# nightlight_bjt_b1.net
KiCad netlist of a schematic drawn in EAGLE
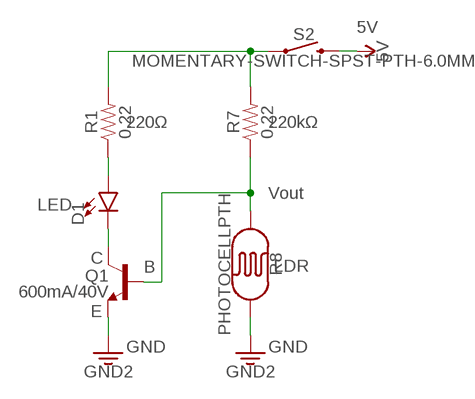
[diagram p0: schematic, sheet 1]

(export (version "E")
  (design (tool "Eeschema 10.0.6"))
  (components
    (comp (ref "D1")
      (value "LED5MM")
      (footprint "eagle-import:LED_5MM")
      (libsource (lib "eagle-import") (part "LED5MM"))
    )
    (comp (ref "Q1")
      (value "600mA/40V")
      (footprint "eagle-import:TO-92")
      (libsource (lib "eagle-import") (part "TRANS_NPN-P2N2222A"))
    )
    (comp (ref "R1")
      (value "0.22")
      (footprint "eagle-import:0805")
      (libsource (lib "eagle-import") (part "0.22OHM-0805-1/4W-1%"))
    )
    (comp (ref "R7")
      (value "0.22")
      (footprint "eagle-import:0805")
      (libsource (lib "eagle-import") (part "0.22OHM-0805-1/4W-1%"))
    )
    (comp (ref "R8")
      (value "PHOTOCELLPTH")
      (footprint "eagle-import:PHOTOCELL")
      (libsource (lib "eagle-import") (part "PHOTOCELLPTH"))
    )
    (comp (ref "S2")
      (value "MOMENTARY-SWITCH-SPST-PTH-6.0MM")
      (footprint "eagle-import:TACTILE_SWITCH_PTH_6.0MM")
      (libsource (lib "eagle-import") (part "MOMENTARY-SWITCH-SPST-PTH-6.0MM"))
    )
  )
  (nets
    (net (code "1") (name "5V") (class "Default")
      (node (ref "S2") (pin "3") (pinfunction "2_3") (pintype "passive"))
    )
    (net (code "2") (name "GND2") (class "Default")
      (node (ref "Q1") (pin "3") (pinfunction "E_3") (pintype "passive"))
      (node (ref "R8") (pin "2") (pinfunction "P$2_2") (pintype "bidirectional"))
    )
    (net (code "3") (name "Net-(D1-C)") (class "Default")
      (node (ref "D1") (pin "K") (pinfunction "C_K") (pintype "passive"))
      (node (ref "Q1") (pin "1") (pinfunction "C_1") (pintype "passive"))
    )
    (net (code "4") (name "Net-(D1-PadA)") (class "Default")
      (node (ref "D1") (pin "A") (pinfunction "A_A") (pintype "passive"))
      (node (ref "R1") (pin "1") (pinfunction "1_1") (pintype "passive"))
    )
    (net (code "5") (name "Net-(Q1-B)") (class "Default")
      (node (ref "Q1") (pin "2") (pinfunction "B_2") (pintype "passive"))
      (node (ref "R7") (pin "1") (pinfunction "1_1") (pintype "passive"))
      (node (ref "R8") (pin "1") (pinfunction "P$1_1") (pintype "bidirectional"))
    )
    (net (code "6") (name "Net-(R1-Pad2)") (class "Default")
      (node (ref "R1") (pin "2") (pinfunction "2_2") (pintype "passive"))
      (node (ref "R7") (pin "2") (pinfunction "2_2") (pintype "passive"))
      (node (ref "S2") (pin "1") (pinfunction "1_1") (pintype "passive"))
    )
  )
)
